# ESPExtra-0_1.net
KiCad netlist of a schematic drawn in EAGLE
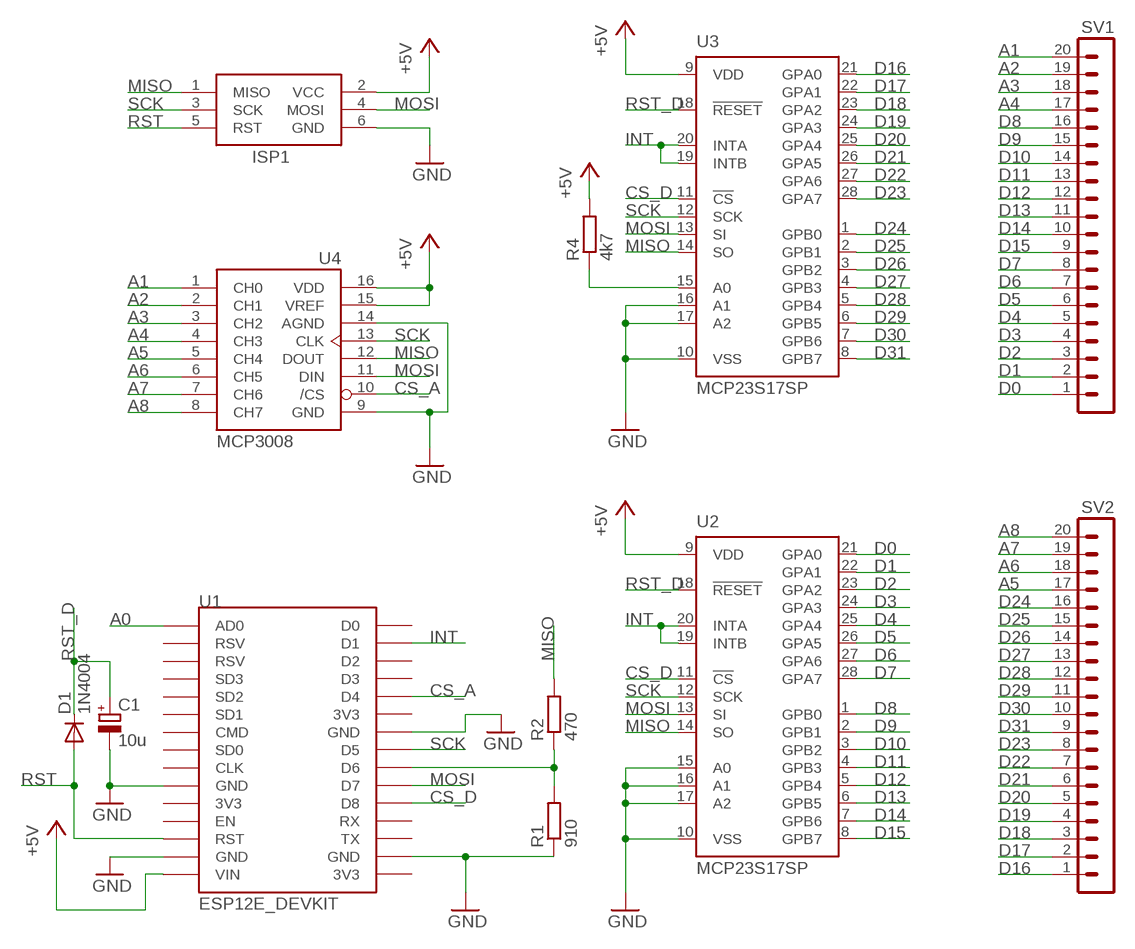
[diagram p0: schematic, sheet 1]

(export (version "E")
  (design (tool "Eeschema 10.0.6"))
  (components
    (comp (ref "C1")
      (value "10u")
      (footprint "eagle-import:E2,5-5")
      (libsource (lib "eagle-import") (part "CPOL-EUE2.5-5"))
    )
    (comp (ref "D1")
      (value "1N4004")
      (footprint "eagle-import:DO41-10")
      (libsource (lib "eagle-import") (part "1N4004"))
    )
    (comp (ref "ISP1")
      (value "AVRISP-6")
      (footprint "eagle-import:AVRISP")
      (libsource (lib "eagle-import") (part "AVRISP-6"))
    )
    (comp (ref "R1")
      (value "910")
      (footprint "eagle-import:0204_5")
      (libsource (lib "eagle-import") (part "R-EU_0204/5"))
    )
    (comp (ref "R2")
      (value "470")
      (footprint "eagle-import:0204_5")
      (libsource (lib "eagle-import") (part "R-EU_0204/5"))
    )
    (comp (ref "R4")
      (value "4k7")
      (footprint "eagle-import:0204_5")
      (libsource (lib "eagle-import") (part "R-EU_0204/5"))
    )
    (comp (ref "SV1")
      (value "MA20-1")
      (footprint "eagle-import:MA20-1")
      (libsource (lib "eagle-import") (part "MA20-1"))
    )
    (comp (ref "SV2")
      (value "MA20-1")
      (footprint "eagle-import:MA20-1")
      (libsource (lib "eagle-import") (part "MA20-1"))
    )
    (comp (ref "U1")
      (value "ESP12E_DEVKIT")
      (footprint "eagle-import:ESP12E_DEVKIT")
      (libsource (lib "eagle-import") (part "ESP12E_DEVKIT"))
    )
    (comp (ref "U2")
      (value "MCP23S17SP")
      (footprint "eagle-import:DIL28-3")
      (fields (field (name "MF") "MICROCHIP") (field (name "MPN") "MCP23S17-E/SP"))
      (libsource (lib "eagle-import") (part "MCP23S17SP"))
    )
    (comp (ref "U3")
      (value "MCP23S17SP")
      (footprint "eagle-import:DIL28-3")
      (fields (field (name "MF") "MICROCHIP") (field (name "MPN") "MCP23S17-E/SP"))
      (libsource (lib "eagle-import") (part "MCP23S17SP"))
    )
    (comp (ref "U4")
      (value "MCP3008")
      (footprint "eagle-import:DIL16")
      (libsource (lib "eagle-import") (part "MCP3008"))
    )
  )
  (nets
    (net (code "1") (name "+5V") (class "Default")
      (node (ref "ISP1") (pin "2") (pinfunction "VCC_2") (pintype "power_in"))
      (node (ref "R4") (pin "2") (pinfunction "2_2") (pintype "passive"))
      (node (ref "U1") (pin "VIN") (pinfunction "VIN_VIN") (pintype "bidirectional"))
      (node (ref "U2") (pin "9") (pinfunction "VDD_9") (pintype "power_in"))
      (node (ref "U3") (pin "9") (pinfunction "VDD_9") (pintype "power_in"))
      (node (ref "U4") (pin "15") (pinfunction "VREF_15") (pintype "input"))
      (node (ref "U4") (pin "16") (pinfunction "VDD_16") (pintype "power_in"))
    )
    (net (code "2") (name "/A0") (class "Default")
      (node (ref "U1") (pin "AD0") (pinfunction "AD0_AD0") (pintype "bidirectional"))
    )
    (net (code "3") (name "/A1") (class "Default")
      (node (ref "SV1") (pin "20") (pinfunction "20_20") (pintype "passive"))
      (node (ref "U4") (pin "1") (pinfunction "CH0_1") (pintype "input"))
    )
    (net (code "4") (name "/A2") (class "Default")
      (node (ref "SV1") (pin "19") (pinfunction "19_19") (pintype "passive"))
      (node (ref "U4") (pin "2") (pinfunction "CH1_2") (pintype "input"))
    )
    (net (code "5") (name "/A3") (class "Default")
      (node (ref "SV1") (pin "18") (pinfunction "18_18") (pintype "passive"))
      (node (ref "U4") (pin "3") (pinfunction "CH2_3") (pintype "input"))
    )
    (net (code "6") (name "/A4") (class "Default")
      (node (ref "SV1") (pin "17") (pinfunction "17_17") (pintype "passive"))
      (node (ref "U4") (pin "4") (pinfunction "CH3_4") (pintype "input"))
    )
    (net (code "7") (name "/A5") (class "Default")
      (node (ref "SV2") (pin "17") (pinfunction "17_17") (pintype "passive"))
      (node (ref "U4") (pin "5") (pinfunction "CH4_5") (pintype "input"))
    )
    (net (code "8") (name "/A6") (class "Default")
      (node (ref "SV2") (pin "18") (pinfunction "18_18") (pintype "passive"))
      (node (ref "U4") (pin "6") (pinfunction "CH5_6") (pintype "input"))
    )
    (net (code "9") (name "/A7") (class "Default")
      (node (ref "SV2") (pin "19") (pinfunction "19_19") (pintype "passive"))
      (node (ref "U4") (pin "7") (pinfunction "CH6_7") (pintype "input"))
    )
    (net (code "10") (name "/A8") (class "Default")
      (node (ref "SV2") (pin "20") (pinfunction "20_20") (pintype "passive"))
      (node (ref "U4") (pin "8") (pinfunction "CH7_8") (pintype "input"))
    )
    (net (code "11") (name "/CS_A") (class "Default")
      (node (ref "U1") (pin "D4") (pinfunction "D4_D4") (pintype "bidirectional"))
      (node (ref "U4") (pin "10") (pinfunction "/CS_10") (pintype "input"))
    )
    (net (code "12") (name "/CS_D") (class "Default")
      (node (ref "U1") (pin "D8") (pinfunction "D8_D8") (pintype "bidirectional"))
      (node (ref "U2") (pin "11") (pinfunction "~{CS}_11") (pintype "input"))
      (node (ref "U3") (pin "11") (pinfunction "~{CS}_11") (pintype "input"))
    )
    (net (code "13") (name "/D0") (class "Default")
      (node (ref "SV1") (pin "1") (pinfunction "1_1") (pintype "passive"))
      (node (ref "U2") (pin "21") (pinfunction "GPA0_21") (pintype "bidirectional"))
    )
    (net (code "14") (name "/D1") (class "Default")
      (node (ref "SV1") (pin "2") (pinfunction "2_2") (pintype "passive"))
      (node (ref "U2") (pin "22") (pinfunction "GPA1_22") (pintype "bidirectional"))
    )
    (net (code "15") (name "/D2") (class "Default")
      (node (ref "SV1") (pin "3") (pinfunction "3_3") (pintype "passive"))
      (node (ref "U2") (pin "23") (pinfunction "GPA2_23") (pintype "bidirectional"))
    )
    (net (code "16") (name "/D3") (class "Default")
      (node (ref "SV1") (pin "4") (pinfunction "4_4") (pintype "passive"))
      (node (ref "U2") (pin "24") (pinfunction "GPA3_24") (pintype "bidirectional"))
    )
    (net (code "17") (name "/D4") (class "Default")
      (node (ref "SV1") (pin "5") (pinfunction "5_5") (pintype "passive"))
      (node (ref "U2") (pin "25") (pinfunction "GPA4_25") (pintype "bidirectional"))
    )
    (net (code "18") (name "/D5") (class "Default")
      (node (ref "SV1") (pin "6") (pinfunction "6_6") (pintype "passive"))
      (node (ref "U2") (pin "26") (pinfunction "GPA5_26") (pintype "bidirectional"))
    )
    (net (code "19") (name "/D6") (class "Default")
      (node (ref "SV1") (pin "7") (pinfunction "7_7") (pintype "passive"))
      (node (ref "U2") (pin "27") (pinfunction "GPA6_27") (pintype "bidirectional"))
    )
    (net (code "20") (name "/D7") (class "Default")
      (node (ref "SV1") (pin "8") (pinfunction "8_8") (pintype "passive"))
      (node (ref "U2") (pin "28") (pinfunction "GPA7_28") (pintype "bidirectional"))
    )
    (net (code "21") (name "/D8") (class "Default")
      (node (ref "SV1") (pin "16") (pinfunction "16_16") (pintype "passive"))
      (node (ref "U2") (pin "1") (pinfunction "GPB0_1") (pintype "bidirectional"))
    )
    (net (code "22") (name "/D9") (class "Default")
      (node (ref "SV1") (pin "15") (pinfunction "15_15") (pintype "passive"))
      (node (ref "U2") (pin "2") (pinfunction "GPB1_2") (pintype "bidirectional"))
    )
    (net (code "23") (name "/D10") (class "Default")
      (node (ref "SV1") (pin "14") (pinfunction "14_14") (pintype "passive"))
      (node (ref "U2") (pin "3") (pinfunction "GPB2_3") (pintype "bidirectional"))
    )
    (net (code "24") (name "/D11") (class "Default")
      (node (ref "SV1") (pin "13") (pinfunction "13_13") (pintype "passive"))
      (node (ref "U2") (pin "4") (pinfunction "GPB3_4") (pintype "bidirectional"))
    )
    (net (code "25") (name "/D12") (class "Default")
      (node (ref "SV1") (pin "12") (pinfunction "12_12") (pintype "passive"))
      (node (ref "U2") (pin "5") (pinfunction "GPB4_5") (pintype "bidirectional"))
    )
    (net (code "26") (name "/D13") (class "Default")
      (node (ref "SV1") (pin "11") (pinfunction "11_11") (pintype "passive"))
      (node (ref "U2") (pin "6") (pinfunction "GPB5_6") (pintype "bidirectional"))
    )
    (net (code "27") (name "/D14") (class "Default")
      (node (ref "SV1") (pin "10") (pinfunction "10_10") (pintype "passive"))
      (node (ref "U2") (pin "7") (pinfunction "GPB6_7") (pintype "bidirectional"))
    )
    (net (code "28") (name "/D15") (class "Default")
      (node (ref "SV1") (pin "9") (pinfunction "9_9") (pintype "passive"))
      (node (ref "U2") (pin "8") (pinfunction "GPB7_8") (pintype "bidirectional"))
    )
    (net (code "29") (name "/D16") (class "Default")
      (node (ref "SV2") (pin "1") (pinfunction "1_1") (pintype "passive"))
      (node (ref "U3") (pin "21") (pinfunction "GPA0_21") (pintype "bidirectional"))
    )
    (net (code "30") (name "/D17") (class "Default")
      (node (ref "SV2") (pin "2") (pinfunction "2_2") (pintype "passive"))
      (node (ref "U3") (pin "22") (pinfunction "GPA1_22") (pintype "bidirectional"))
    )
    (net (code "31") (name "/D18") (class "Default")
      (node (ref "SV2") (pin "3") (pinfunction "3_3") (pintype "passive"))
      (node (ref "U3") (pin "23") (pinfunction "GPA2_23") (pintype "bidirectional"))
    )
    (net (code "32") (name "/D19") (class "Default")
      (node (ref "SV2") (pin "4") (pinfunction "4_4") (pintype "passive"))
      (node (ref "U3") (pin "24") (pinfunction "GPA3_24") (pintype "bidirectional"))
    )
    (net (code "33") (name "/D20") (class "Default")
      (node (ref "SV2") (pin "5") (pinfunction "5_5") (pintype "passive"))
      (node (ref "U3") (pin "25") (pinfunction "GPA4_25") (pintype "bidirectional"))
    )
    (net (code "34") (name "/D21") (class "Default")
      (node (ref "SV2") (pin "6") (pinfunction "6_6") (pintype "passive"))
      (node (ref "U3") (pin "26") (pinfunction "GPA5_26") (pintype "bidirectional"))
    )
    (net (code "35") (name "/D22") (class "Default")
      (node (ref "SV2") (pin "7") (pinfunction "7_7") (pintype "passive"))
      (node (ref "U3") (pin "27") (pinfunction "GPA6_27") (pintype "bidirectional"))
    )
    (net (code "36") (name "/D23") (class "Default")
      (node (ref "SV2") (pin "8") (pinfunction "8_8") (pintype "passive"))
      (node (ref "U3") (pin "28") (pinfunction "GPA7_28") (pintype "bidirectional"))
    )
    (net (code "37") (name "/D24") (class "Default")
      (node (ref "SV2") (pin "16") (pinfunction "16_16") (pintype "passive"))
      (node (ref "U3") (pin "1") (pinfunction "GPB0_1") (pintype "bidirectional"))
    )
    (net (code "38") (name "/D25") (class "Default")
      (node (ref "SV2") (pin "15") (pinfunction "15_15") (pintype "passive"))
      (node (ref "U3") (pin "2") (pinfunction "GPB1_2") (pintype "bidirectional"))
    )
    (net (code "39") (name "/D26") (class "Default")
      (node (ref "SV2") (pin "14") (pinfunction "14_14") (pintype "passive"))
      (node (ref "U3") (pin "3") (pinfunction "GPB2_3") (pintype "bidirectional"))
    )
    (net (code "40") (name "/D27") (class "Default")
      (node (ref "SV2") (pin "13") (pinfunction "13_13") (pintype "passive"))
      (node (ref "U3") (pin "4") (pinfunction "GPB3_4") (pintype "bidirectional"))
    )
    (net (code "41") (name "/D28") (class "Default")
      (node (ref "SV2") (pin "12") (pinfunction "12_12") (pintype "passive"))
      (node (ref "U3") (pin "5") (pinfunction "GPB4_5") (pintype "bidirectional"))
    )
    (net (code "42") (name "/D29") (class "Default")
      (node (ref "SV2") (pin "11") (pinfunction "11_11") (pintype "passive"))
      (node (ref "U3") (pin "6") (pinfunction "GPB5_6") (pintype "bidirectional"))
    )
    (net (code "43") (name "/D30") (class "Default")
      (node (ref "SV2") (pin "10") (pinfunction "10_10") (pintype "passive"))
      (node (ref "U3") (pin "7") (pinfunction "GPB6_7") (pintype "bidirectional"))
    )
    (net (code "44") (name "/D31") (class "Default")
      (node (ref "SV2") (pin "9") (pinfunction "9_9") (pintype "passive"))
      (node (ref "U3") (pin "8") (pinfunction "GPB7_8") (pintype "bidirectional"))
    )
    (net (code "45") (name "/INT") (class "Default")
      (node (ref "U1") (pin "D1") (pinfunction "D1_D1") (pintype "bidirectional"))
      (node (ref "U2") (pin "19") (pinfunction "INTB_19") (pintype "output"))
      (node (ref "U2") (pin "20") (pinfunction "INTA_20") (pintype "output"))
      (node (ref "U3") (pin "19") (pinfunction "INTB_19") (pintype "output"))
      (node (ref "U3") (pin "20") (pinfunction "INTA_20") (pintype "output"))
    )
    (net (code "46") (name "/MISO") (class "Default")
      (node (ref "ISP1") (pin "1") (pinfunction "MISO_1") (pintype "input"))
      (node (ref "R2") (pin "2") (pinfunction "2_2") (pintype "passive"))
      (node (ref "U2") (pin "14") (pinfunction "SO_14") (pintype "output"))
      (node (ref "U3") (pin "14") (pinfunction "SO_14") (pintype "output"))
      (node (ref "U4") (pin "12") (pinfunction "DOUT_12") (pintype "output"))
    )
    (net (code "47") (name "/MOSI") (class "Default")
      (node (ref "ISP1") (pin "4") (pinfunction "MOSI_4") (pintype "output"))
      (node (ref "U1") (pin "D7") (pinfunction "D7_D7") (pintype "bidirectional"))
      (node (ref "U2") (pin "13") (pinfunction "SI_13") (pintype "input"))
      (node (ref "U3") (pin "13") (pinfunction "SI_13") (pintype "input"))
      (node (ref "U4") (pin "11") (pinfunction "DIN_11") (pintype "input"))
    )
    (net (code "48") (name "/RST") (class "Default")
      (node (ref "D1") (pin "A") (pinfunction "A_A") (pintype "passive"))
      (node (ref "ISP1") (pin "5") (pinfunction "RST_5") (pintype "output"))
      (node (ref "U1") (pin "RST") (pinfunction "RST_RST") (pintype "bidirectional"))
    )
    (net (code "49") (name "/RST_D") (class "Default")
      (node (ref "C1") (pin "+") (pinfunction "+_+") (pintype "passive"))
      (node (ref "D1") (pin "C") (pinfunction "C_C") (pintype "passive"))
      (node (ref "U2") (pin "18") (pinfunction "~{RESET}_18") (pintype "input"))
      (node (ref "U3") (pin "18") (pinfunction "~{RESET}_18") (pintype "input"))
    )
    (net (code "50") (name "/SCK") (class "Default")
      (node (ref "ISP1") (pin "3") (pinfunction "SCK_3") (pintype "output"))
      (node (ref "U1") (pin "D5") (pinfunction "D5_D5") (pintype "bidirectional"))
      (node (ref "U2") (pin "12") (pinfunction "SCK_12") (pintype "input"))
      (node (ref "U3") (pin "12") (pinfunction "SCK_12") (pintype "input"))
      (node (ref "U4") (pin "13") (pinfunction "CLK_13") (pintype "input"))
    )
    (net (code "51") (name "GND") (class "Default")
      (node (ref "C1") (pin "-") (pinfunction "-_-") (pintype "passive"))
      (node (ref "ISP1") (pin "6") (pinfunction "GND_6") (pintype "power_in"))
      (node (ref "R1") (pin "1") (pinfunction "1_1") (pintype "passive"))
      (node (ref "U1") (pin "GND@0") (pinfunction "GND_GND@0") (pintype "bidirectional"))
      (node (ref "U1") (pin "GND@1") (pinfunction "GND_GND@1") (pintype "bidirectional"))
      (node (ref "U1") (pin "GND@2") (pinfunction "GND_GND@2") (pintype "bidirectional"))
      (node (ref "U1") (pin "GND@3") (pinfunction "GND_GND@3") (pintype "bidirectional"))
      (node (ref "U2") (pin "10") (pinfunction "VSS_10") (pintype "power_in"))
      (node (ref "U2") (pin "15") (pinfunction "A0_15") (pintype "input"))
      (node (ref "U2") (pin "16") (pinfunction "A1_16") (pintype "input"))
      (node (ref "U2") (pin "17") (pinfunction "A2_17") (pintype "input"))
      (node (ref "U3") (pin "10") (pinfunction "VSS_10") (pintype "power_in"))
      (node (ref "U3") (pin "16") (pinfunction "A1_16") (pintype "input"))
      (node (ref "U3") (pin "17") (pinfunction "A2_17") (pintype "input"))
      (node (ref "U4") (pin "14") (pinfunction "AGND_14") (pintype "power_in"))
      (node (ref "U4") (pin "9") (pinfunction "GND_9") (pintype "power_in"))
    )
    (net (code "52") (name "Net-(R1-Pad2)") (class "Default")
      (node (ref "R1") (pin "2") (pinfunction "2_2") (pintype "passive"))
      (node (ref "R2") (pin "1") (pinfunction "1_1") (pintype "passive"))
      (node (ref "U1") (pin "D6") (pinfunction "D6_D6") (pintype "bidirectional"))
    )
    (net (code "53") (name "Net-(U3-A0)") (class "Default")
      (node (ref "R4") (pin "1") (pinfunction "1_1") (pintype "passive"))
      (node (ref "U3") (pin "15") (pinfunction "A0_15") (pintype "input"))
    )
    (net (code "54") (name "unconnected-(U1-3V3-Pad3V3@0)") (class "Default")
      (node (ref "U1") (pin "3V3@0") (pinfunction "3V3_3V3@0") (pintype "bidirectional"))
    )
    (net (code "55") (name "unconnected-(U1-3V3-Pad3V3@1)") (class "Default")
      (node (ref "U1") (pin "3V3@1") (pinfunction "3V3_3V3@1") (pintype "bidirectional"))
    )
    (net (code "56") (name "unconnected-(U1-3V3-Pad3V3@2)") (class "Default")
      (node (ref "U1") (pin "3V3@2") (pinfunction "3V3_3V3@2") (pintype "bidirectional"))
    )
    (net (code "57") (name "unconnected-(U1-PadCLK)") (class "Default")
      (node (ref "U1") (pin "CLK") (pinfunction "CLK_CLK") (pintype "bidirectional"))
    )
    (net (code "58") (name "unconnected-(U1-PadCMD)") (class "Default")
      (node (ref "U1") (pin "CMD") (pinfunction "CMD_CMD") (pintype "bidirectional"))
    )
    (net (code "59") (name "unconnected-(U1-PadD0)") (class "Default")
      (node (ref "U1") (pin "D0") (pinfunction "D0_D0") (pintype "bidirectional"))
    )
    (net (code "60") (name "unconnected-(U1-PadD2)") (class "Default")
      (node (ref "U1") (pin "D2") (pinfunction "D2_D2") (pintype "bidirectional"))
    )
    (net (code "61") (name "unconnected-(U1-PadD3)") (class "Default")
      (node (ref "U1") (pin "D3") (pinfunction "D3_D3") (pintype "bidirectional"))
    )
    (net (code "62") (name "unconnected-(U1-PadEN)") (class "Default")
      (node (ref "U1") (pin "EN") (pinfunction "EN_EN") (pintype "bidirectional"))
    )
    (net (code "63") (name "unconnected-(U1-PadRX)") (class "Default")
      (node (ref "U1") (pin "RX") (pinfunction "RX_RX") (pintype "bidirectional"))
    )
    (net (code "64") (name "unconnected-(U1-PadSD0)") (class "Default")
      (node (ref "U1") (pin "SD0") (pinfunction "SD0_SD0") (pintype "bidirectional"))
    )
    (net (code "65") (name "unconnected-(U1-PadSD1)") (class "Default")
      (node (ref "U1") (pin "SD1") (pinfunction "SD1_SD1") (pintype "bidirectional"))
    )
    (net (code "66") (name "unconnected-(U1-PadSD2)") (class "Default")
      (node (ref "U1") (pin "SD2") (pinfunction "SD2_SD2") (pintype "bidirectional"))
    )
    (net (code "67") (name "unconnected-(U1-PadSD3)") (class "Default")
      (node (ref "U1") (pin "SD3") (pinfunction "SD3_SD3") (pintype "bidirectional"))
    )
    (net (code "68") (name "unconnected-(U1-PadTX)") (class "Default")
      (node (ref "U1") (pin "TX") (pinfunction "TX_TX") (pintype "bidirectional"))
    )
    (net (code "69") (name "unconnected-(U1-RSV-PadRSV@0)") (class "Default")
      (node (ref "U1") (pin "RSV@0") (pinfunction "RSV_RSV@0") (pintype "bidirectional"))
    )
    (net (code "70") (name "unconnected-(U1-RSV-PadRSV@1)") (class "Default")
      (node (ref "U1") (pin "RSV@1") (pinfunction "RSV_RSV@1") (pintype "bidirectional"))
    )
  )
)
